# bms_FET_R00.net
KiCad netlist of a schematic drawn in Altium Designer
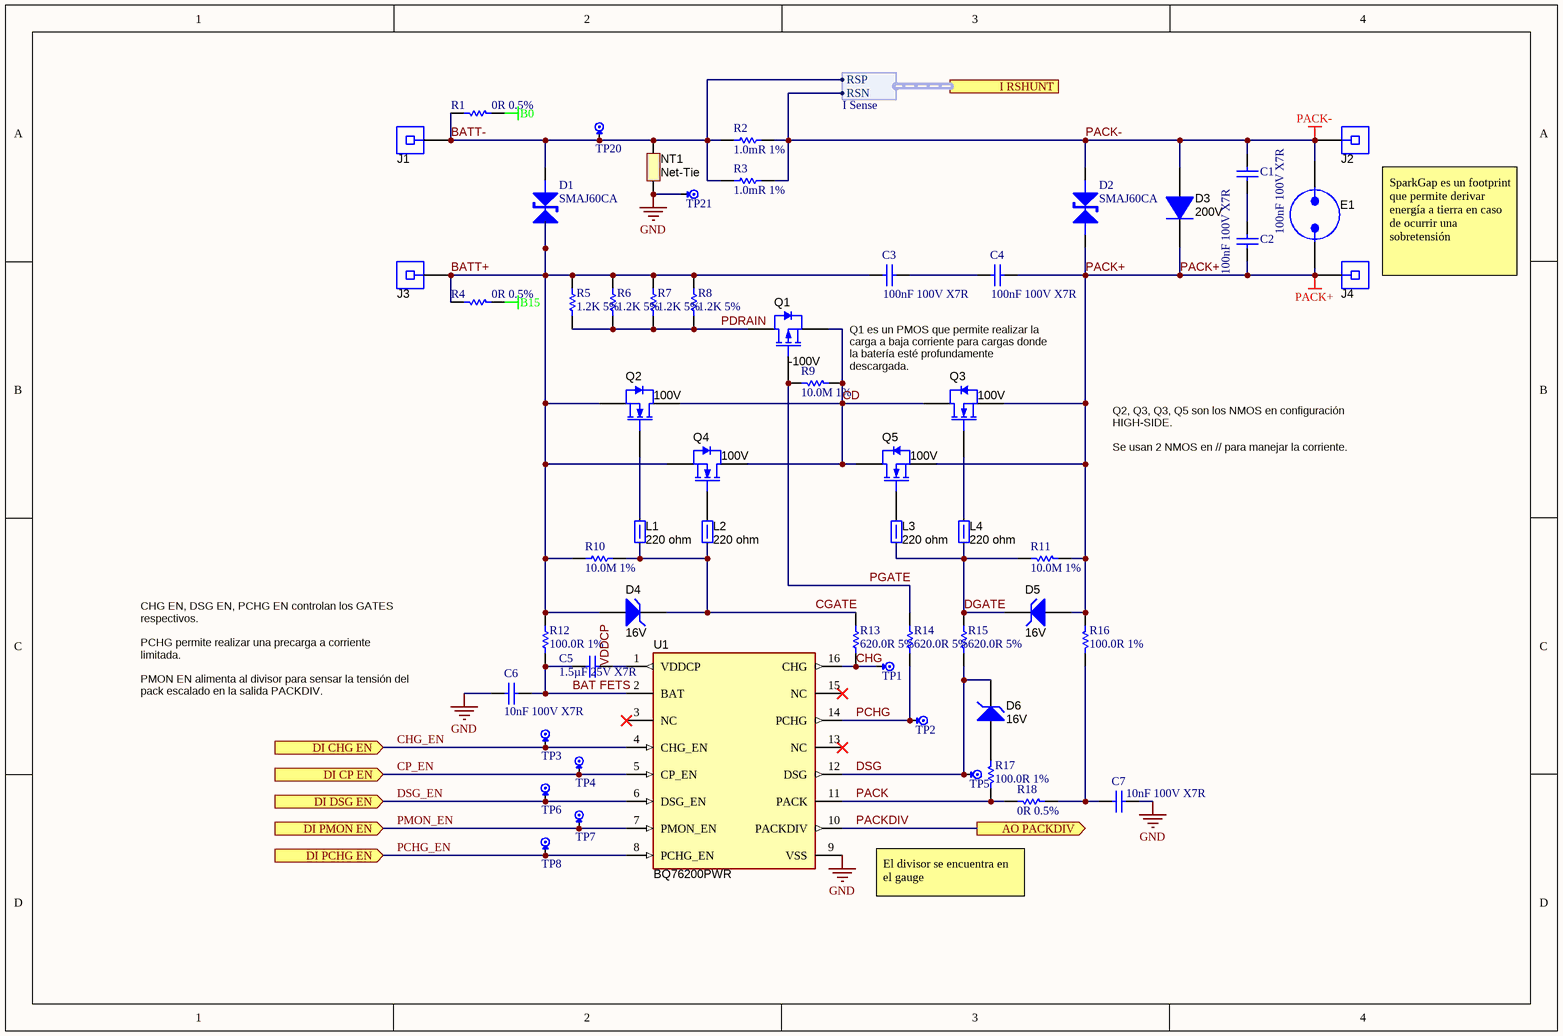
[diagram p0: bms_FET_R00.SchDoc]

(export (version "E")
  (design (tool "Eeschema 10.0.6"))
  (components
    (comp (ref "C1")
      (value "100nF 100V X7R")
      (footprint "C0603")
      (description "Capacitor")
      (libsource (lib "capacitors") (part "Cap 0603"))
    )
    (comp (ref "C2")
      (value "100nF 100V X7R")
      (footprint "C0603")
      (description "Capacitor")
      (libsource (lib "capacitors") (part "Cap 0603"))
    )
    (comp (ref "C3")
      (value "100nF 100V X7R")
      (footprint "C0603")
      (description "Capacitor")
      (libsource (lib "capacitors") (part "Cap 0603"))
    )
    (comp (ref "C4")
      (value "100nF 100V X7R")
      (footprint "C0603")
      (description "Capacitor")
      (libsource (lib "capacitors") (part "Cap 0603"))
    )
    (comp (ref "C5")
      (value "1.5µF 25V X7R")
      (footprint "0805_HV_2")
      (description "Capacitor")
      (libsource (lib "capacitors") (part "Cap 0805_HV"))
    )
    (comp (ref "C6")
      (value "10nF 100V X7R")
      (footprint "0805_HV_2")
      (description "Capacitor")
      (libsource (lib "capacitors") (part "Cap 0805_HV"))
    )
    (comp (ref "C7")
      (value "10nF 100V X7R")
      (footprint "0805_HV_2")
      (description "Capacitor")
      (libsource (lib "capacitors") (part "Cap 0805_HV"))
    )
    (comp (ref "D1")
      (value "SMAJ60CA")
      (footprint "DO-214AB(SMA)")
      (description "TVS DIODE 22VWM 35.5VC DO214AC.\r\nBIDIRECCIONAL")
      (libsource (lib "diodes") (part "SMAJ60CA"))
    )
    (comp (ref "D2")
      (value "SMAJ60CA")
      (footprint "DO-214AB(SMA)")
      (description "TVS DIODE 22VWM 35.5VC DO214AC.\r\nBIDIRECCIONAL")
      (libsource (lib "diodes") (part "SMAJ60CA"))
    )
    (comp (ref "D3")
      (value "200V")
      (footprint "SMC")
      (description "Diode, Ultrafast, 200V, 3A, SMC")
      (fields
        (field (name "PARTNUMBER") "ES3D-E3/57T")
        (field (name "MANUFACTURER") "Vishay-Semiconductor")
        (field (name "PUBLISHER") "Texas Instruments")
      )
      (libsource (lib "diodes") (part "ES3D-E3/57T"))
    )
    (comp (ref "D4")
      (value "16V")
      (footprint "sod-323")
      (description "Diode, Zener, 16 V, 200 mW, SOD-323")
      (fields
        (field (name "PARTNUMBER") "MMSZ5246BS-7-F")
        (field (name "MANUFACTURER") "Diodes Inc.")
        (field (name "SYMBOLCREATOR") "a0412235")
        (field (name "PUBLISHER") "Texas Instruments")
      )
      (libsource (lib "diodes") (part "MMSZ5246BS-7-F"))
    )
    (comp (ref "D5")
      (value "16V")
      (footprint "sod-323")
      (description "Diode, Zener, 16 V, 200 mW, SOD-323")
      (fields
        (field (name "PARTNUMBER") "MMSZ5246BS-7-F")
        (field (name "MANUFACTURER") "Diodes Inc.")
        (field (name "SYMBOLCREATOR") "a0412235")
        (field (name "PUBLISHER") "Texas Instruments")
      )
      (libsource (lib "diodes") (part "MMSZ5246BS-7-F"))
    )
    (comp (ref "D6")
      (value "16V")
      (footprint "sod-323")
      (description "Diode, Zener, 16 V, 200 mW, SOD-323")
      (fields
        (field (name "PARTNUMBER") "MMSZ5246BS-7-F")
        (field (name "MANUFACTURER") "Diodes Inc.")
        (field (name "SYMBOLCREATOR") "a0412235")
        (field (name "PUBLISHER") "Texas Instruments")
      )
      (libsource (lib "diodes") (part "MMSZ5246BS-7-F"))
    )
    (comp (ref "E1")
      (value "N/A")
      (footprint "SPARK_GAP2")
      (description "Spark Gap")
      (fields (field (name "SYMBOLCREATOR") "a0412235") (field (name "PUBLISHER") "Texas Instruments"))
      (libsource (lib "connectors") (part "SparkGap"))
    )
    (comp (ref "J1")
      (value "L35")
      (footprint "TB_L35")
      (description "Connector, L Type Copper Single Conductor, TH")
      (fields
        (field (name "MANUFACTURER") "Thomas & Betts")
        (field (name "SYMBOLCREATOR") "a0799628")
        (field (name "PUBLISHER") "Texas Instruments")
      )
      (libsource (lib "connectors") (part "L35"))
    )
    (comp (ref "J2")
      (value "L35")
      (footprint "TB_L35")
      (description "Connector, L Type Copper Single Conductor, TH")
      (fields
        (field (name "MANUFACTURER") "Thomas & Betts")
        (field (name "SYMBOLCREATOR") "a0799628")
        (field (name "PUBLISHER") "Texas Instruments")
      )
      (libsource (lib "") (part "L35_1"))
    )
    (comp (ref "J3")
      (value "L35")
      (footprint "TB_L35")
      (description "Connector, L Type Copper Single Conductor, TH")
      (fields
        (field (name "MANUFACTURER") "Thomas & Betts")
        (field (name "SYMBOLCREATOR") "a0799628")
        (field (name "PUBLISHER") "Texas Instruments")
      )
      (libsource (lib "connectors") (part "L35"))
    )
    (comp (ref "J4")
      (value "L35")
      (footprint "TB_L35")
      (description "Connector, L Type Copper Single Conductor, TH")
      (fields
        (field (name "MANUFACTURER") "Thomas & Betts")
        (field (name "SYMBOLCREATOR") "a0799628")
        (field (name "PUBLISHER") "Texas Instruments")
      )
      (libsource (lib "") (part "L35_1"))
    )
    (comp (ref "L1")
      (value "220 ohm")
      (footprint "0603 FB")
      (description "Ferrite Bead, 220 ohm @ 100 MHz, 2.5 A, 0603")
      (fields
        (field (name "PARTNUMBER") "BLM18SG221TN1D")
        (field (name "MANUFACTURER") "MuRata")
        (field (name "PUBLISHER") "Texas Instruments")
      )
      (libsource (lib "inductors") (part "BLM18SG221TN1D"))
    )
    (comp (ref "L2")
      (value "220 ohm")
      (footprint "0603 FB")
      (description "Ferrite Bead, 220 ohm @ 100 MHz, 2.5 A, 0603")
      (fields
        (field (name "PARTNUMBER") "BLM18SG221TN1D")
        (field (name "MANUFACTURER") "MuRata")
        (field (name "PUBLISHER") "Texas Instruments")
      )
      (libsource (lib "inductors") (part "BLM18SG221TN1D"))
    )
    (comp (ref "L3")
      (value "220 ohm")
      (footprint "0603 FB")
      (description "Ferrite Bead, 220 ohm @ 100 MHz, 2.5 A, 0603")
      (fields
        (field (name "PARTNUMBER") "BLM18SG221TN1D")
        (field (name "MANUFACTURER") "MuRata")
        (field (name "PUBLISHER") "Texas Instruments")
      )
      (libsource (lib "inductors") (part "BLM18SG221TN1D"))
    )
    (comp (ref "L4")
      (value "220 ohm")
      (footprint "0603 FB")
      (description "Ferrite Bead, 220 ohm @ 100 MHz, 2.5 A, 0603")
      (fields
        (field (name "PARTNUMBER") "BLM18SG221TN1D")
        (field (name "MANUFACTURER") "MuRata")
        (field (name "PUBLISHER") "Texas Instruments")
      )
      (libsource (lib "inductors") (part "BLM18SG221TN1D"))
    )
    (comp (ref "NT1")
      (value "Net-Tie")
      (footprint "Net-Tie_50milWide_30milLong")
      (description "Single point connection between nets.")
      (fields (field (name "SYMBOLCREATOR") "codlsc") (field (name "PUBLISHER") "Texas Instruments"))
      (libsource (lib "connectors") (part "Net-Tie"))
    )
    (comp (ref "Q1")
      (value "-100V")
      (footprint "SOT-23")
      (description "MOSFET, P-CH, -100V, -0.6A, SOT-23")
      (fields
        (field (name "PARTNUMBER") "ZXMP10A13FTA")
        (field (name "MANUFACTURER") "Diodes Inc.")
        (field (name "PUBLISHER") "Texas Instruments")
      )
      (libsource (lib "pmos") (part "ZXMP10A13FTA"))
    )
    (comp (ref "Q2")
      (value "100V")
      (footprint "KTT0002A_N")
      (description "MOSFET, N-CH, 100 V, 200 A, KTT0002A")
      (fields
        (field (name "PARTNUMBER") "CSD19536KTT")
        (field (name "MANUFACTURER") "Texas Instruments")
        (field (name "PUBLISHER") "Texas Instruments")
      )
      (libsource (lib "nmos") (part "CSD19536KTT"))
    )
    (comp (ref "Q3")
      (value "100V")
      (footprint "KTT0002A_N")
      (description "MOSFET, N-CH, 100 V, 200 A, KTT0002A")
      (fields
        (field (name "PARTNUMBER") "CSD19536KTT")
        (field (name "MANUFACTURER") "Texas Instruments")
        (field (name "PUBLISHER") "Texas Instruments")
      )
      (libsource (lib "nmos") (part "CSD19536KTT"))
    )
    (comp (ref "Q4")
      (value "100V")
      (footprint "KTT0002A_N")
      (description "MOSFET, N-CH, 100 V, 200 A, KTT0002A")
      (fields
        (field (name "PARTNUMBER") "CSD19536KTT")
        (field (name "MANUFACTURER") "Texas Instruments")
        (field (name "PUBLISHER") "Texas Instruments")
      )
      (libsource (lib "nmos") (part "CSD19536KTT"))
    )
    (comp (ref "Q5")
      (value "100V")
      (footprint "KTT0002A_N")
      (description "MOSFET, N-CH, 100 V, 200 A, KTT0002A")
      (fields
        (field (name "PARTNUMBER") "CSD19536KTT")
        (field (name "MANUFACTURER") "Texas Instruments")
        (field (name "PUBLISHER") "Texas Instruments")
      )
      (libsource (lib "nmos") (part "CSD19536KTT"))
    )
    (comp (ref "R1")
      (value "0R 0.5%")
      (footprint "R0603")
      (description "Resistor")
      (libsource (lib "resistors") (part "Res"))
    )
    (comp (ref "R2")
      (value "1.0mR 1%")
      (footprint "2010")
      (description "Resistor")
      (libsource (lib "resistors") (part "Res"))
    )
    (comp (ref "R3")
      (value "1.0mR 1%")
      (footprint "2010")
      (description "Resistor")
      (libsource (lib "resistors") (part "Res"))
    )
    (comp (ref "R4")
      (value "0R 0.5%")
      (footprint "R0603")
      (description "Resistor")
      (libsource (lib "resistors") (part "Res"))
    )
    (comp (ref "R5")
      (value "1.2K 5%")
      (footprint "2512")
      (description "Resistor")
      (libsource (lib "resistors") (part "Res"))
    )
    (comp (ref "R6")
      (value "1.2K 5%")
      (footprint "2512")
      (description "Resistor")
      (libsource (lib "resistors") (part "Res"))
    )
    (comp (ref "R7")
      (value "1.2K 5%")
      (footprint "2512")
      (description "Resistor")
      (libsource (lib "resistors") (part "Res"))
    )
    (comp (ref "R8")
      (value "1.2K 5%")
      (footprint "2512")
      (description "Resistor")
      (libsource (lib "resistors") (part "Res"))
    )
    (comp (ref "R9")
      (value "10.0M 1%")
      (footprint "R0603")
      (description "Resistor")
      (libsource (lib "resistors") (part "Res"))
    )
    (comp (ref "R10")
      (value "10.0M 1%")
      (footprint "R0603")
      (description "Resistor")
      (libsource (lib "resistors") (part "Res"))
    )
    (comp (ref "R11")
      (value "10.0M 1%")
      (footprint "R0603")
      (description "Resistor")
      (libsource (lib "resistors") (part "Res"))
    )
    (comp (ref "R12")
      (value "100.0R 1%")
      (footprint "R0603")
      (description "Resistor")
      (libsource (lib "resistors") (part "Res"))
    )
    (comp (ref "R13")
      (value "620.0R 5%")
      (footprint "R0603")
      (description "Resistor")
      (libsource (lib "resistors") (part "Res"))
    )
    (comp (ref "R14")
      (value "620.0R 5%")
      (footprint "R0603")
      (description "Resistor")
      (libsource (lib "resistors") (part "Res"))
    )
    (comp (ref "R15")
      (value "620.0R 5%")
      (footprint "R0603")
      (description "Resistor")
      (libsource (lib "resistors") (part "Res"))
    )
    (comp (ref "R16")
      (value "100.0R 1%")
      (footprint "R0603")
      (description "Resistor")
      (libsource (lib "resistors") (part "Res"))
    )
    (comp (ref "R17")
      (value "100.0R 1%")
      (footprint "R0603")
      (description "Resistor")
      (libsource (lib "resistors") (part "Res"))
    )
    (comp (ref "R18")
      (value "0R 0.5%")
      (footprint "R0603")
      (description "Resistor")
      (libsource (lib "resistors") (part "Res"))
    )
    (comp (ref "TP1")
      (value "Test Point")
      (footprint "TEST POINT SMD 1")
      (libsource (lib "connectors") (part "Test Point"))
    )
    (comp (ref "TP2")
      (value "Test Point")
      (footprint "TEST POINT SMD 1")
      (libsource (lib "connectors") (part "Test Point"))
    )
    (comp (ref "TP3")
      (value "Test Point")
      (footprint "TEST POINT SMD 1")
      (libsource (lib "connectors") (part "Test Point"))
    )
    (comp (ref "TP4")
      (value "Test Point")
      (footprint "TEST POINT SMD 1")
      (libsource (lib "connectors") (part "Test Point"))
    )
    (comp (ref "TP5")
      (value "Test Point")
      (footprint "TEST POINT SMD 1")
      (libsource (lib "connectors") (part "Test Point"))
    )
    (comp (ref "TP6")
      (value "Test Point")
      (footprint "TEST POINT SMD 1")
      (libsource (lib "connectors") (part "Test Point"))
    )
    (comp (ref "TP7")
      (value "Test Point")
      (footprint "TEST POINT SMD 1")
      (libsource (lib "connectors") (part "Test Point"))
    )
    (comp (ref "TP8")
      (value "Test Point")
      (footprint "TEST POINT SMD 1")
      (libsource (lib "connectors") (part "Test Point"))
    )
    (comp (ref "TP20")
      (value "Test Point")
      (footprint "TEST POINT SMD 1")
      (libsource (lib "connectors") (part "Test Point"))
    )
    (comp (ref "TP21")
      (value "Test Point")
      (footprint "TEST POINT SMD 1")
      (libsource (lib "connectors") (part "Test Point"))
    )
    (comp (ref "U1")
      (value "BQ76200PWR")
      (footprint "PW0016A_N")
      (description "bq76200: Low-Power, High-Side N-channel FET Driver with Pack Voltage Monitor, PW0016A")
      (fields
        (field (name "ALTERNATE PARTNUMBER") "BQ76200PW")
        (field (name "MANUFACTURER") "Texas Instruments")
        (field (name "SYMBOLCREATOR") "x0208325")
        (field (name "PUBLISHER") "Texas Instruments")
      )
      (libsource (lib "integrated_circuits") (part "BQ76200PWR"))
    )
  )
  (nets
    (net (code "3") (name "/BAT FETS") (class "Default")
      (node (ref "C5") (pin "1") (pinfunction "1_1") (pintype "passive"))
      (node (ref "C6") (pin "2") (pinfunction "2_2") (pintype "passive"))
      (node (ref "R12") (pin "1") (pinfunction "1_1") (pintype "passive"))
      (node (ref "U1") (pin "2") (pinfunction "BAT_2") (pintype "power_in"))
    )
    (net (code "4") (name "/BATT+") (class "Default")
      (node (ref "C3") (pin "1") (pinfunction "1_1") (pintype "passive"))
      (node (ref "D1") (pin "K") (pintype "passive"))
      (node (ref "D4") (pin "2") (pinfunction "A_2") (pintype "passive"))
      (node (ref "J3") (pin "1") (pinfunction "1_1") (pintype "passive"))
      (node (ref "Q2") (pin "3") (pinfunction "S_3") (pintype "passive"))
      (node (ref "Q4") (pin "3") (pinfunction "S_3") (pintype "passive"))
      (node (ref "R10") (pin "2") (pinfunction "2_2") (pintype "passive"))
      (node (ref "R12") (pin "2") (pinfunction "2_2") (pintype "passive"))
      (node (ref "R4") (pin "1") (pinfunction "1_1") (pintype "passive"))
      (node (ref "R5") (pin "2") (pinfunction "2_2") (pintype "passive"))
      (node (ref "R6") (pin "2") (pinfunction "2_2") (pintype "passive"))
      (node (ref "R7") (pin "2") (pinfunction "2_2") (pintype "passive"))
      (node (ref "R8") (pin "2") (pinfunction "2_2") (pintype "passive"))
    )
    (net (code "5") (name "/BATT-") (class "Default")
      (node (ref "D1") (pin "A") (pintype "passive"))
      (node (ref "J1") (pin "1") (pinfunction "1_1") (pintype "passive"))
      (node (ref "NT1") (pin "2") (pinfunction "2_2") (pintype "passive"))
      (node (ref "R1") (pin "1") (pinfunction "1_1") (pintype "passive"))
      (node (ref "R2") (pin "1") (pinfunction "1_1") (pintype "passive"))
      (node (ref "R3") (pin "1") (pinfunction "1_1") (pintype "passive"))
      (node (ref "TP20") (pin "1") (pinfunction "1_1") (pintype "passive"))
    )
    (net (code "6") (name "/CD") (class "Default")
      (node (ref "Q1") (pin "2") (pinfunction "S_2") (pintype "passive"))
      (node (ref "Q2") (pin "2") (pinfunction "D_2") (pintype "passive"))
      (node (ref "Q3") (pin "2") (pinfunction "D_2") (pintype "passive"))
      (node (ref "Q4") (pin "2") (pinfunction "D_2") (pintype "passive"))
      (node (ref "Q5") (pin "2") (pinfunction "D_2") (pintype "passive"))
      (node (ref "R9") (pin "2") (pinfunction "2_2") (pintype "passive"))
    )
    (net (code "7") (name "/CGATE") (class "Default")
      (node (ref "D4") (pin "1") (pinfunction "K_1") (pintype "passive"))
      (node (ref "L1") (pin "1") (pinfunction "1_1") (pintype "passive"))
      (node (ref "L2") (pin "1") (pinfunction "1_1") (pintype "passive"))
      (node (ref "R10") (pin "1") (pinfunction "1_1") (pintype "passive"))
      (node (ref "R13") (pin "1") (pinfunction "1_1") (pintype "passive"))
    )
    (net (code "8") (name "/CHG") (class "Default")
      (node (ref "R13") (pin "2") (pinfunction "2_2") (pintype "passive"))
      (node (ref "TP1") (pin "1") (pinfunction "1_1") (pintype "passive"))
      (node (ref "U1") (pin "16") (pinfunction "CHG_16") (pintype "output"))
    )
    (net (code "9") (name "/CHG_EN") (class "Default")
      (node (ref "TP3") (pin "1") (pinfunction "1_1") (pintype "passive"))
      (node (ref "U1") (pin "4") (pinfunction "CHG_EN_4") (pintype "input"))
    )
    (net (code "10") (name "/CP_EN") (class "Default")
      (node (ref "TP4") (pin "1") (pinfunction "1_1") (pintype "passive"))
      (node (ref "U1") (pin "5") (pinfunction "CP_EN_5") (pintype "input"))
    )
    (net (code "11") (name "/DGATE") (class "Default")
      (node (ref "D5") (pin "1") (pinfunction "K_1") (pintype "passive"))
      (node (ref "L3") (pin "1") (pinfunction "1_1") (pintype "passive"))
      (node (ref "L4") (pin "1") (pinfunction "1_1") (pintype "passive"))
      (node (ref "R11") (pin "1") (pinfunction "1_1") (pintype "passive"))
      (node (ref "R15") (pin "1") (pinfunction "1_1") (pintype "passive"))
    )
    (net (code "12") (name "/DSG") (class "Default")
      (node (ref "D6") (pin "1") (pinfunction "K_1") (pintype "passive"))
      (node (ref "R15") (pin "2") (pinfunction "2_2") (pintype "passive"))
      (node (ref "TP5") (pin "1") (pinfunction "1_1") (pintype "passive"))
      (node (ref "U1") (pin "12") (pinfunction "DSG_12") (pintype "output"))
    )
    (net (code "13") (name "/DSG_EN") (class "Default")
      (node (ref "TP6") (pin "1") (pinfunction "1_1") (pintype "passive"))
      (node (ref "U1") (pin "6") (pinfunction "DSG_EN_6") (pintype "input"))
    )
    (net (code "14") (name "/PACK") (class "Default")
      (node (ref "R17") (pin "1") (pinfunction "1_1") (pintype "passive"))
      (node (ref "R18") (pin "2") (pinfunction "2_2") (pintype "passive"))
      (node (ref "U1") (pin "11") (pinfunction "PACK_11") (pintype "power_in"))
    )
    (net (code "15") (name "/PACKDIV") (class "Default")
      (node (ref "U1") (pin "10") (pinfunction "PACKDIV_10") (pintype "output"))
    )
    (net (code "16") (name "/PCHG") (class "Default")
      (node (ref "R14") (pin "2") (pinfunction "2_2") (pintype "passive"))
      (node (ref "TP2") (pin "1") (pinfunction "1_1") (pintype "passive"))
      (node (ref "U1") (pin "14") (pinfunction "PCHG_14") (pintype "output"))
    )
    (net (code "17") (name "/PCHG_EN") (class "Default")
      (node (ref "TP8") (pin "1") (pinfunction "1_1") (pintype "passive"))
      (node (ref "U1") (pin "8") (pinfunction "PCHG_EN_8") (pintype "input"))
    )
    (net (code "18") (name "/PDRAIN") (class "Default")
      (node (ref "Q1") (pin "3") (pinfunction "D_3") (pintype "passive"))
      (node (ref "R5") (pin "1") (pinfunction "1_1") (pintype "passive"))
      (node (ref "R6") (pin "1") (pinfunction "1_1") (pintype "passive"))
      (node (ref "R7") (pin "1") (pinfunction "1_1") (pintype "passive"))
      (node (ref "R8") (pin "1") (pinfunction "1_1") (pintype "passive"))
    )
    (net (code "19") (name "/PGATE") (class "Default")
      (node (ref "Q1") (pin "1") (pinfunction "G_1") (pintype "passive"))
      (node (ref "R14") (pin "1") (pinfunction "1_1") (pintype "passive"))
      (node (ref "R9") (pin "1") (pinfunction "1_1") (pintype "passive"))
    )
    (net (code "20") (name "/PMON_EN") (class "Default")
      (node (ref "TP7") (pin "1") (pinfunction "1_1") (pintype "passive"))
      (node (ref "U1") (pin "7") (pinfunction "PMON_EN_7") (pintype "input"))
    )
    (net (code "21") (name "/VDDCP") (class "Default")
      (node (ref "C5") (pin "2") (pinfunction "2_2") (pintype "passive"))
      (node (ref "U1") (pin "1") (pinfunction "VDDCP_1") (pintype "output"))
    )
    (net (code "23") (name "B0") (class "Default")
      (node (ref "R1") (pin "2") (pinfunction "2_2") (pintype "passive"))
    )
    (net (code "24") (name "B15") (class "Default")
      (node (ref "R4") (pin "2") (pinfunction "2_2") (pintype "passive"))
    )
    (net (code "25") (name "GND") (class "Default")
      (node (ref "C6") (pin "1") (pinfunction "1_1") (pintype "passive"))
      (node (ref "C7") (pin "2") (pinfunction "2_2") (pintype "passive"))
      (node (ref "NT1") (pin "1") (pinfunction "1_1") (pintype "passive"))
      (node (ref "TP21") (pin "1") (pinfunction "1_1") (pintype "passive"))
      (node (ref "U1") (pin "9") (pinfunction "VSS_9") (pintype "power_in"))
    )
    (net (code "26") (name "Net-(C1-Pad1)") (class "Default")
      (node (ref "C1") (pin "1") (pinfunction "1_1") (pintype "passive"))
      (node (ref "C2") (pin "2") (pinfunction "2_2") (pintype "passive"))
    )
    (net (code "27") (name "Net-(C3-Pad2)") (class "Default")
      (node (ref "C3") (pin "2") (pinfunction "2_2") (pintype "passive"))
      (node (ref "C4") (pin "1") (pinfunction "1_1") (pintype "passive"))
    )
    (net (code "28") (name "Net-(C7-Pad1)") (class "Default")
      (node (ref "C7") (pin "1") (pinfunction "1_1") (pintype "passive"))
      (node (ref "R16") (pin "1") (pinfunction "1_1") (pintype "passive"))
      (node (ref "R18") (pin "1") (pinfunction "1_1") (pintype "passive"))
    )
    (net (code "29") (name "Net-(D6-A)") (class "Default")
      (node (ref "D6") (pin "2") (pinfunction "A_2") (pintype "passive"))
      (node (ref "R17") (pin "2") (pinfunction "2_2") (pintype "passive"))
    )
    (net (code "30") (name "Net-(Q2-G)") (class "Default")
      (node (ref "L1") (pin "2") (pinfunction "2_2") (pintype "passive"))
      (node (ref "Q2") (pin "1") (pinfunction "G_1") (pintype "passive"))
    )
    (net (code "31") (name "Net-(Q3-G)") (class "Default")
      (node (ref "L4") (pin "2") (pinfunction "2_2") (pintype "passive"))
      (node (ref "Q3") (pin "1") (pinfunction "G_1") (pintype "passive"))
    )
    (net (code "32") (name "Net-(Q4-G)") (class "Default")
      (node (ref "L2") (pin "2") (pinfunction "2_2") (pintype "passive"))
      (node (ref "Q4") (pin "1") (pinfunction "G_1") (pintype "passive"))
    )
    (net (code "33") (name "Net-(Q5-G)") (class "Default")
      (node (ref "L3") (pin "2") (pinfunction "2_2") (pintype "passive"))
      (node (ref "Q5") (pin "1") (pinfunction "G_1") (pintype "passive"))
    )
    (net (code "34") (name "PACK+") (class "Default")
      (node (ref "C2") (pin "1") (pinfunction "1_1") (pintype "passive"))
      (node (ref "C4") (pin "2") (pinfunction "2_2") (pintype "passive"))
      (node (ref "D2") (pin "K") (pintype "passive"))
      (node (ref "D3") (pin "1") (pinfunction "K_1") (pintype "passive"))
      (node (ref "D5") (pin "2") (pinfunction "A_2") (pintype "passive"))
      (node (ref "E1") (pin "1") (pinfunction "1_1") (pintype "passive"))
      (node (ref "J4") (pin "1") (pinfunction "1_1") (pintype "passive"))
      (node (ref "Q3") (pin "3") (pinfunction "S_3") (pintype "passive"))
      (node (ref "Q5") (pin "3") (pinfunction "S_3") (pintype "passive"))
      (node (ref "R11") (pin "2") (pinfunction "2_2") (pintype "passive"))
      (node (ref "R16") (pin "2") (pinfunction "2_2") (pintype "passive"))
    )
    (net (code "35") (name "PACK-") (class "Default")
      (node (ref "C1") (pin "2") (pinfunction "2_2") (pintype "passive"))
      (node (ref "D2") (pin "A") (pintype "passive"))
      (node (ref "D3") (pin "2") (pinfunction "A_2") (pintype "passive"))
      (node (ref "E1") (pin "2") (pinfunction "2_2") (pintype "passive"))
      (node (ref "J2") (pin "1") (pinfunction "1_1") (pintype "passive"))
      (node (ref "R2") (pin "2") (pinfunction "2_2") (pintype "passive"))
      (node (ref "R3") (pin "2") (pinfunction "2_2") (pintype "passive"))
    )
    (net (code "36") (name "unconnected-(U1-NC-Pad3)") (class "Default")
      (node (ref "U1") (pin "3") (pinfunction "NC_3") (pintype "passive+no_connect"))
    )
    (net (code "37") (name "unconnected-(U1-NC-Pad13)") (class "Default")
      (node (ref "U1") (pin "13") (pinfunction "NC_13") (pintype "passive+no_connect"))
    )
    (net (code "38") (name "unconnected-(U1-NC-Pad15)") (class "Default")
      (node (ref "U1") (pin "15") (pinfunction "NC_15") (pintype "passive+no_connect"))
    )
  )
)
